# audio_in.net
KiCad netlist of a schematic drawn in Altium Designer
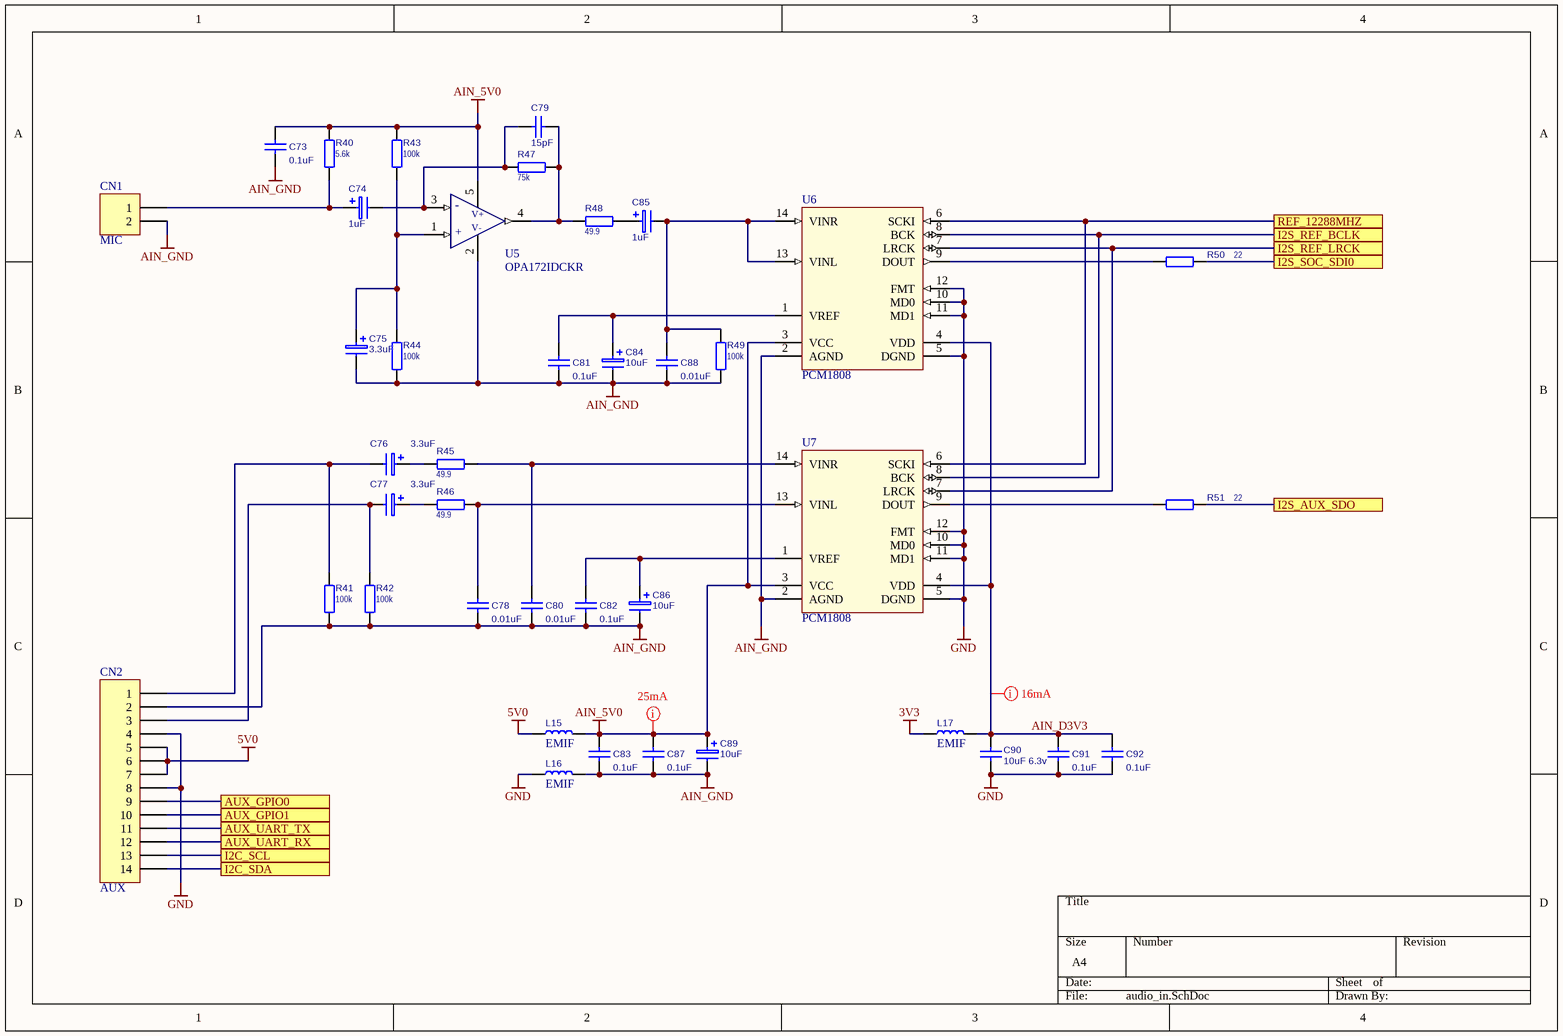
[diagram p0: audio_in.SchDoc]

(export (version "E")
  (design (tool "Eeschema 10.0.6"))
  (components
    (comp (ref "C73")
      (value "0.1uF")
      (footprint "Capacitors:C0603")
      (description "CAP_NPOL")
      (fields (field (name "Comment") "CC0603KRX7R9BB104"))
      (libsource (lib "capacitors") (part "CAP_NPOL"))
    )
    (comp (ref "C74")
      (value "1uF")
      (footprint "Capacitors:ALUM_4")
      (description "CAP_POL")
      (libsource (lib "capacitors") (part "CAP_POL"))
    )
    (comp (ref "C75")
      (value "3.3uF")
      (footprint "Capacitors:ALUM_3.3")
      (description "CAP_POL")
      (libsource (lib "capacitors") (part "CAP_POL"))
    )
    (comp (ref "C76")
      (value "3.3uF")
      (footprint "ALUM_3.3")
      (description "CAP_POL")
      (fields (field (name "Comment") "UWT1V3R3MCL2B"))
      (libsource (lib "capacitors") (part "CAP_POL"))
    )
    (comp (ref "C77")
      (value "3.3uF")
      (footprint "ALUM_3.3")
      (description "CAP_POL")
      (fields (field (name "Comment") "UWT1V3R3MCL2B"))
      (libsource (lib "capacitors") (part "CAP_POL"))
    )
    (comp (ref "C78")
      (value "0.01uF")
      (footprint "Capacitors:C0603")
      (description "CAP_NPOL")
      (fields (field (name "Comment") "CL10B103KB8NNNC"))
      (libsource (lib "capacitors") (part "CAP_NPOL"))
    )
    (comp (ref "C79")
      (value "15pF")
      (footprint "Capacitors:C0603")
      (description "CAP_NPOL")
      (fields (field (name "Comment") "CC0603GRNPO9BN150"))
      (libsource (lib "capacitors") (part "CAP_NPOL"))
    )
    (comp (ref "C80")
      (value "0.01uF")
      (footprint "Capacitors:C0603")
      (description "CAP_NPOL")
      (fields (field (name "Comment") "CL10B103KB8NNNC"))
      (libsource (lib "capacitors") (part "CAP_NPOL"))
    )
    (comp (ref "C81")
      (value "0.1uF")
      (footprint "Capacitors:C0603")
      (description "CAP_NPOL")
      (fields (field (name "Comment") "CC0603KRX7R9BB104"))
      (libsource (lib "capacitors") (part "CAP_NPOL"))
    )
    (comp (ref "C82")
      (value "0.1uF")
      (footprint "Capacitors:C0603")
      (description "CAP_NPOL")
      (fields (field (name "Comment") "CC0603KRX7R9BB104"))
      (libsource (lib "capacitors") (part "CAP_NPOL"))
    )
    (comp (ref "C83")
      (value "0.1uF")
      (footprint "Capacitors:C0603")
      (description "CAP_NPOL")
      (fields (field (name "Comment") "CC0603KRX7R9BB104"))
      (libsource (lib "capacitors") (part "CAP_NPOL"))
    )
    (comp (ref "C84")
      (value "10uF")
      (footprint "Capacitors:ALUM_4")
      (description "CAP_POL")
      (fields (field (name "Comment") "CB016M0010RSB-0405"))
      (libsource (lib "capacitors") (part "CAP_POL"))
    )
    (comp (ref "C85")
      (value "1uF")
      (footprint "Capacitors:ALUM_4")
      (description "CAP_POL")
      (libsource (lib "capacitors") (part "CAP_POL"))
    )
    (comp (ref "C86")
      (value "10uF")
      (footprint "ALUM_4")
      (description "CAP_POL")
      (fields (field (name "Comment") "CB016M0010RSB-0405"))
      (libsource (lib "capacitors") (part "CAP_POL"))
    )
    (comp (ref "C87")
      (value "0.1uF")
      (footprint "Capacitors:C0603")
      (description "CAP_NPOL")
      (fields (field (name "Comment") "CC0603KRX7R9BB104"))
      (libsource (lib "capacitors") (part "CAP_NPOL"))
    )
    (comp (ref "C88")
      (value "0.01uF")
      (footprint "Capacitors:C0603")
      (description "CAP_NPOL")
      (fields (field (name "Comment") "CL10B103KB8NNNC"))
      (libsource (lib "capacitors") (part "CAP_NPOL"))
    )
    (comp (ref "C89")
      (value "10uF")
      (footprint "Capacitors:ALUM_3.3")
      (description "CAP_POL")
      (fields (field (name "Comment") "CB016M0010RSB-0405"))
      (libsource (lib "capacitors") (part "CAP_POL"))
    )
    (comp (ref "C90")
      (value "10uF 6.3v")
      (footprint "Capacitors:C0603")
      (description "CAP_NPOL")
      (fields (field (name "Comment") "CC0603MRX5R5BB106"))
      (libsource (lib "capacitors") (part "CAP_NPOL"))
    )
    (comp (ref "C91")
      (value "0.1uF")
      (footprint "Capacitors:C0603")
      (description "CAP_NPOL")
      (fields (field (name "Comment") "CC0603KRX7R9BB104"))
      (libsource (lib "capacitors") (part "CAP_NPOL"))
    )
    (comp (ref "C92")
      (value "0.1uF")
      (footprint "Capacitors:C0603")
      (description "CAP_NPOL")
      (fields (field (name "Comment") "CC0603KRX7R9BB104"))
      (libsource (lib "capacitors") (part "CAP_NPOL"))
    )
    (comp (ref "CN1")
      (value "MIC")
      (footprint "DG308-2.54-2P")
      (description "Header, 2-Pin")
      (fields (field (name "PUBLISHER") "Altium Limited"))
      (libsource (lib "HDR") (part "HDR 2"))
    )
    (comp (ref "CN2")
      (value "AUX")
      (footprint "PLS-14R")
      (description "Header, 14-Pin")
      (fields (field (name "PUBLISHER") "Altium Limited"))
      (libsource (lib "HDR") (part "HDR 14"))
    )
    (comp (ref "L15")
      (value "EMIF")
      (footprint "IND0603")
      (description "IND_WO_IRON")
      (fields (field (name "Comment") "BLM18AG102SN1D"))
      (libsource (lib "inductors") (part "IND_WO_IRON"))
    )
    (comp (ref "L16")
      (value "EMIF")
      (footprint "IND0603")
      (description "IND_WO_IRON")
      (fields (field (name "Comment") "BLM18AG102SN1D"))
      (libsource (lib "inductors") (part "IND_WO_IRON"))
    )
    (comp (ref "L17")
      (value "EMIF")
      (footprint "IND0603")
      (description "IND_WO_IRON")
      (fields (field (name "Comment") "BLM18AG102SN1D"))
      (libsource (lib "inductors") (part "IND_WO_IRON"))
    )
    (comp (ref "R40")
      (value "5.6k")
      (footprint "R0603")
      (description "RES")
      (libsource (lib "resistors") (part "RESISTOR"))
    )
    (comp (ref "R41")
      (value "100k")
      (footprint "R0603")
      (description "RES")
      (libsource (lib "resistors") (part "RESISTOR"))
    )
    (comp (ref "R42")
      (value "100k")
      (footprint "R0603")
      (description "RES")
      (libsource (lib "resistors") (part "RESISTOR"))
    )
    (comp (ref "R43")
      (value "100k")
      (footprint "R0603")
      (description "RES")
      (libsource (lib "resistors") (part "RESISTOR"))
    )
    (comp (ref "R44")
      (value "100k")
      (footprint "R0603")
      (description "RES")
      (libsource (lib "resistors") (part "RESISTOR"))
    )
    (comp (ref "R45")
      (value "49.9")
      (footprint "R0603")
      (description "RES")
      (libsource (lib "resistors") (part "RESISTOR"))
    )
    (comp (ref "R46")
      (value "49.9")
      (footprint "R0603")
      (description "RES")
      (libsource (lib "resistors") (part "RESISTOR"))
    )
    (comp (ref "R47")
      (value "75k")
      (footprint "R0603")
      (description "RES")
      (libsource (lib "resistors") (part "RESISTOR"))
    )
    (comp (ref "R48")
      (value "49.9")
      (footprint "R0603")
      (description "RES")
      (libsource (lib "resistors") (part "RESISTOR"))
    )
    (comp (ref "R49")
      (value "100k")
      (footprint "R0603")
      (description "RES")
      (libsource (lib "resistors") (part "RESISTOR"))
    )
    (comp (ref "R50")
      (value "22")
      (footprint "R0603")
      (description "RES")
      (libsource (lib "resistors") (part "RESISTOR"))
    )
    (comp (ref "R51")
      (value "22")
      (footprint "R0603")
      (description "RES")
      (libsource (lib "resistors") (part "RESISTOR"))
    )
    (comp (ref "U5")
      (value "OPA172IDCKR")
      (footprint "SC70:SC70-5")
      (description "OPAx172 36-V, Single-Supply, 10-MHz, Rail-to-Rail Output Operational Amplifiers")
      (libsource (lib "OPA172") (part "OPA172IDCKR"))
    )
    (comp (ref "U6")
      (value "PCM1808")
      (footprint "TSSOP-14")
      (description "PCM1808 Single-Ended, Analog-Input 24-Bit, 96-kHz Stereo ADC")
      (libsource (lib "PCM1808") (part "PCM1808"))
    )
    (comp (ref "U7")
      (value "PCM1808")
      (footprint "TSSOP-14")
      (description "PCM1808 Single-Ended, Analog-Input 24-Bit, 96-kHz Stereo ADC")
      (libsource (lib "PCM1808") (part "PCM1808"))
    )
  )
  (nets
    (net (code "1") (name "/AIN_D3V3") (class "Default")
      (node (ref "C90") (pin "2") (pinfunction "2_2") (pintype "passive"))
      (node (ref "C91") (pin "1") (pinfunction "1_1") (pintype "passive"))
      (node (ref "C92") (pin "1") (pinfunction "1_1") (pintype "passive"))
      (node (ref "L17") (pin "1") (pintype "passive"))
      (node (ref "U6") (pin "4") (pinfunction "VDD_4") (pintype "power_in"))
      (node (ref "U7") (pin "4") (pinfunction "VDD_4") (pintype "power_in"))
    )
    (net (code "2") (name "/AUX_GPIO0") (class "Default")
      (node (ref "CN2") (pin "9") (pinfunction "9_9") (pintype "passive"))
    )
    (net (code "3") (name "/AUX_GPIO1") (class "Default")
      (node (ref "CN2") (pin "10") (pinfunction "10_10") (pintype "passive"))
    )
    (net (code "4") (name "/AUX_UART_RX") (class "Default")
      (node (ref "CN2") (pin "12") (pinfunction "12_12") (pintype "passive"))
    )
    (net (code "5") (name "/AUX_UART_TX") (class "Default")
      (node (ref "CN2") (pin "11") (pinfunction "11_11") (pintype "passive"))
    )
    (net (code "6") (name "/I2C_SCL") (class "Default")
      (node (ref "CN2") (pin "13") (pinfunction "13_13") (pintype "passive"))
    )
    (net (code "7") (name "/I2C_SDA") (class "Default")
      (node (ref "CN2") (pin "14") (pinfunction "14_14") (pintype "passive"))
    )
    (net (code "8") (name "/I2S_AUX_SDO") (class "Default")
      (node (ref "R51") (pin "2") (pinfunction "2_2") (pintype "passive"))
    )
    (net (code "9") (name "/I2S_REF_BCLK") (class "Default")
      (node (ref "U6") (pin "8") (pinfunction "BCK_8") (pintype "bidirectional"))
      (node (ref "U7") (pin "8") (pinfunction "BCK_8") (pintype "bidirectional"))
    )
    (net (code "10") (name "/I2S_REF_LRCK") (class "Default")
      (node (ref "U6") (pin "7") (pinfunction "LRCK_7") (pintype "bidirectional"))
      (node (ref "U7") (pin "7") (pinfunction "LRCK_7") (pintype "bidirectional"))
    )
    (net (code "11") (name "/I2S_SOC_SDI0") (class "Default")
      (node (ref "R50") (pin "2") (pinfunction "2_2") (pintype "passive"))
    )
    (net (code "12") (name "/REF_12288MHZ") (class "Default")
      (node (ref "U6") (pin "6") (pinfunction "SCKI_6") (pintype "input"))
      (node (ref "U7") (pin "6") (pinfunction "SCKI_6") (pintype "input"))
    )
    (net (code "13") (name "3V3") (class "Default") (node (ref "L17") (pin "2") (pintype "passive")))
    (net (code "14") (name "5V0") (class "Default")
      (node (ref "CN2") (pin "5") (pinfunction "5_5") (pintype "passive"))
      (node (ref "CN2") (pin "6") (pinfunction "6_6") (pintype "passive"))
      (node (ref "CN2") (pin "7") (pinfunction "7_7") (pintype "passive"))
      (node (ref "L15") (pin "2") (pintype "passive"))
    )
    (net (code "15") (name "AIN_5V0") (class "Default")
      (node (ref "C73") (pin "1") (pinfunction "1_1") (pintype "passive"))
      (node (ref "C83") (pin "1") (pinfunction "1_1") (pintype "passive"))
      (node (ref "C87") (pin "1") (pinfunction "1_1") (pintype "passive"))
      (node (ref "C89") (pin "1") (pinfunction "+_1") (pintype "passive"))
      (node (ref "L15") (pin "1") (pintype "passive"))
      (node (ref "R40") (pin "1") (pinfunction "1_1") (pintype "passive"))
      (node (ref "R43") (pin "1") (pinfunction "1_1") (pintype "passive"))
      (node (ref "U5") (pin "5") (pinfunction "V+_5") (pintype "power_in"))
      (node (ref "U6") (pin "3") (pinfunction "VCC_3") (pintype "power_in"))
      (node (ref "U7") (pin "3") (pinfunction "VCC_3") (pintype "power_in"))
    )
    (net (code "16") (name "AIN_GND") (class "Default")
      (node (ref "C73") (pin "2") (pinfunction "2_2") (pintype "passive"))
      (node (ref "C75") (pin "2") (pinfunction "-_2") (pintype "passive"))
      (node (ref "C78") (pin "2") (pinfunction "2_2") (pintype "passive"))
      (node (ref "C80") (pin "2") (pinfunction "2_2") (pintype "passive"))
      (node (ref "C81") (pin "2") (pinfunction "2_2") (pintype "passive"))
      (node (ref "C82") (pin "2") (pinfunction "2_2") (pintype "passive"))
      (node (ref "C83") (pin "2") (pinfunction "2_2") (pintype "passive"))
      (node (ref "C84") (pin "2") (pinfunction "-_2") (pintype "passive"))
      (node (ref "C86") (pin "2") (pinfunction "-_2") (pintype "passive"))
      (node (ref "C87") (pin "2") (pinfunction "2_2") (pintype "passive"))
      (node (ref "C88") (pin "2") (pinfunction "2_2") (pintype "passive"))
      (node (ref "C89") (pin "2") (pinfunction "-_2") (pintype "passive"))
      (node (ref "CN1") (pin "2") (pinfunction "2_2") (pintype "passive"))
      (node (ref "CN2") (pin "2") (pinfunction "2_2") (pintype "passive"))
      (node (ref "L16") (pin "1") (pintype "passive"))
      (node (ref "R41") (pin "2") (pinfunction "2_2") (pintype "passive"))
      (node (ref "R42") (pin "2") (pinfunction "2_2") (pintype "passive"))
      (node (ref "R44") (pin "2") (pinfunction "2_2") (pintype "passive"))
      (node (ref "R49") (pin "2") (pinfunction "2_2") (pintype "passive"))
      (node (ref "U5") (pin "2") (pinfunction "V-_2") (pintype "power_in"))
      (node (ref "U6") (pin "2") (pinfunction "AGND_2") (pintype "power_in"))
      (node (ref "U7") (pin "2") (pinfunction "AGND_2") (pintype "power_in"))
    )
    (net (code "17") (name "GND") (class "Default")
      (node (ref "C90") (pin "1") (pinfunction "1_1") (pintype "passive"))
      (node (ref "C91") (pin "2") (pinfunction "2_2") (pintype "passive"))
      (node (ref "C92") (pin "2") (pinfunction "2_2") (pintype "passive"))
      (node (ref "CN2") (pin "4") (pinfunction "4_4") (pintype "passive"))
      (node (ref "CN2") (pin "8") (pinfunction "8_8") (pintype "passive"))
      (node (ref "L16") (pin "2") (pintype "passive"))
      (node (ref "U6") (pin "10") (pinfunction "MD0_10") (pintype "input"))
      (node (ref "U6") (pin "11") (pinfunction "MD1_11") (pintype "input"))
      (node (ref "U6") (pin "12") (pinfunction "FMT_12") (pintype "input"))
      (node (ref "U6") (pin "5") (pinfunction "DGND_5") (pintype "power_in"))
      (node (ref "U7") (pin "10") (pinfunction "MD0_10") (pintype "input"))
      (node (ref "U7") (pin "11") (pinfunction "MD1_11") (pintype "input"))
      (node (ref "U7") (pin "12") (pinfunction "FMT_12") (pintype "input"))
      (node (ref "U7") (pin "5") (pinfunction "DGND_5") (pintype "power_in"))
    )
    (net (code "18") (name "Net-(C74-+)") (class "Default")
      (node (ref "C74") (pin "1") (pinfunction "+_1") (pintype "passive"))
      (node (ref "CN1") (pin "1") (pinfunction "1_1") (pintype "passive"))
      (node (ref "R40") (pin "2") (pinfunction "2_2") (pintype "passive"))
    )
    (net (code "19") (name "Net-(C74--)") (class "Default")
      (node (ref "C74") (pin "2") (pinfunction "-_2") (pintype "passive"))
      (node (ref "C79") (pin "1") (pinfunction "1_1") (pintype "passive"))
      (node (ref "R47") (pin "2") (pinfunction "2_2") (pintype "passive"))
      (node (ref "U5") (pin "3") (pinfunction "-_3") (pintype "input"))
    )
    (net (code "20") (name "Net-(C75-+)") (class "Default")
      (node (ref "C75") (pin "1") (pinfunction "+_1") (pintype "passive"))
      (node (ref "R43") (pin "2") (pinfunction "2_2") (pintype "passive"))
      (node (ref "R44") (pin "1") (pinfunction "1_1") (pintype "passive"))
      (node (ref "U5") (pin "1") (pinfunction "+_1") (pintype "input"))
    )
    (net (code "21") (name "Net-(C76-+)") (class "Default")
      (node (ref "C76") (pin "1") (pinfunction "+_1") (pintype "passive"))
      (node (ref "R45") (pin "1") (pinfunction "1_1") (pintype "passive"))
    )
    (net (code "22") (name "Net-(C76--)") (class "Default")
      (node (ref "C76") (pin "2") (pinfunction "-_2") (pintype "passive"))
      (node (ref "CN2") (pin "1") (pinfunction "1_1") (pintype "passive"))
      (node (ref "R41") (pin "1") (pinfunction "1_1") (pintype "passive"))
    )
    (net (code "23") (name "Net-(C77-+)") (class "Default")
      (node (ref "C77") (pin "1") (pinfunction "+_1") (pintype "passive"))
      (node (ref "R46") (pin "1") (pinfunction "1_1") (pintype "passive"))
    )
    (net (code "24") (name "Net-(C77--)") (class "Default")
      (node (ref "C77") (pin "2") (pinfunction "-_2") (pintype "passive"))
      (node (ref "CN2") (pin "3") (pinfunction "3_3") (pintype "passive"))
      (node (ref "R42") (pin "1") (pinfunction "1_1") (pintype "passive"))
    )
    (net (code "25") (name "Net-(C79-Pad2)") (class "Default")
      (node (ref "C79") (pin "2") (pinfunction "2_2") (pintype "passive"))
      (node (ref "R47") (pin "1") (pinfunction "1_1") (pintype "passive"))
      (node (ref "R48") (pin "1") (pinfunction "1_1") (pintype "passive"))
      (node (ref "U5") (pin "4") (pintype "output"))
    )
    (net (code "26") (name "Net-(C84-+)") (class "Default")
      (node (ref "C81") (pin "1") (pinfunction "1_1") (pintype "passive"))
      (node (ref "C84") (pin "1") (pinfunction "+_1") (pintype "passive"))
      (node (ref "U6") (pin "1") (pinfunction "VREF_1") (pintype "passive"))
    )
    (net (code "27") (name "Net-(C85-+)") (class "Default")
      (node (ref "C85") (pin "1") (pinfunction "+_1") (pintype "passive"))
      (node (ref "R48") (pin "2") (pinfunction "2_2") (pintype "passive"))
    )
    (net (code "28") (name "Net-(C85--)") (class "Default")
      (node (ref "C85") (pin "2") (pinfunction "-_2") (pintype "passive"))
      (node (ref "C88") (pin "1") (pinfunction "1_1") (pintype "passive"))
      (node (ref "R49") (pin "1") (pinfunction "1_1") (pintype "passive"))
      (node (ref "U6") (pin "13") (pinfunction "VINL_13") (pintype "input"))
      (node (ref "U6") (pin "14") (pinfunction "VINR_14") (pintype "input"))
    )
    (net (code "29") (name "Net-(C86-+)") (class "Default")
      (node (ref "C82") (pin "1") (pinfunction "1_1") (pintype "passive"))
      (node (ref "C86") (pin "1") (pinfunction "+_1") (pintype "passive"))
      (node (ref "U7") (pin "1") (pinfunction "VREF_1") (pintype "passive"))
    )
    (net (code "30") (name "Net-(U6-DOUT)") (class "Default")
      (node (ref "R50") (pin "1") (pinfunction "1_1") (pintype "passive"))
      (node (ref "U6") (pin "9") (pinfunction "DOUT_9") (pintype "output"))
    )
    (net (code "31") (name "Net-(U7-DOUT)") (class "Default")
      (node (ref "R51") (pin "1") (pinfunction "1_1") (pintype "passive"))
      (node (ref "U7") (pin "9") (pinfunction "DOUT_9") (pintype "output"))
    )
    (net (code "32") (name "Net-(U7-VINL)") (class "Default")
      (node (ref "C78") (pin "1") (pinfunction "1_1") (pintype "passive"))
      (node (ref "R46") (pin "2") (pinfunction "2_2") (pintype "passive"))
      (node (ref "U7") (pin "13") (pinfunction "VINL_13") (pintype "input"))
    )
    (net (code "33") (name "Net-(U7-VINR)") (class "Default")
      (node (ref "C80") (pin "1") (pinfunction "1_1") (pintype "passive"))
      (node (ref "R45") (pin "2") (pinfunction "2_2") (pintype "passive"))
      (node (ref "U7") (pin "14") (pinfunction "VINR_14") (pintype "input"))
    )
  )
)
